# ProDoc_HEMY_Brake_Driver_1_1_2025-03-20.net
KiCad netlist of a schematic drawn in EasyEDA Pro
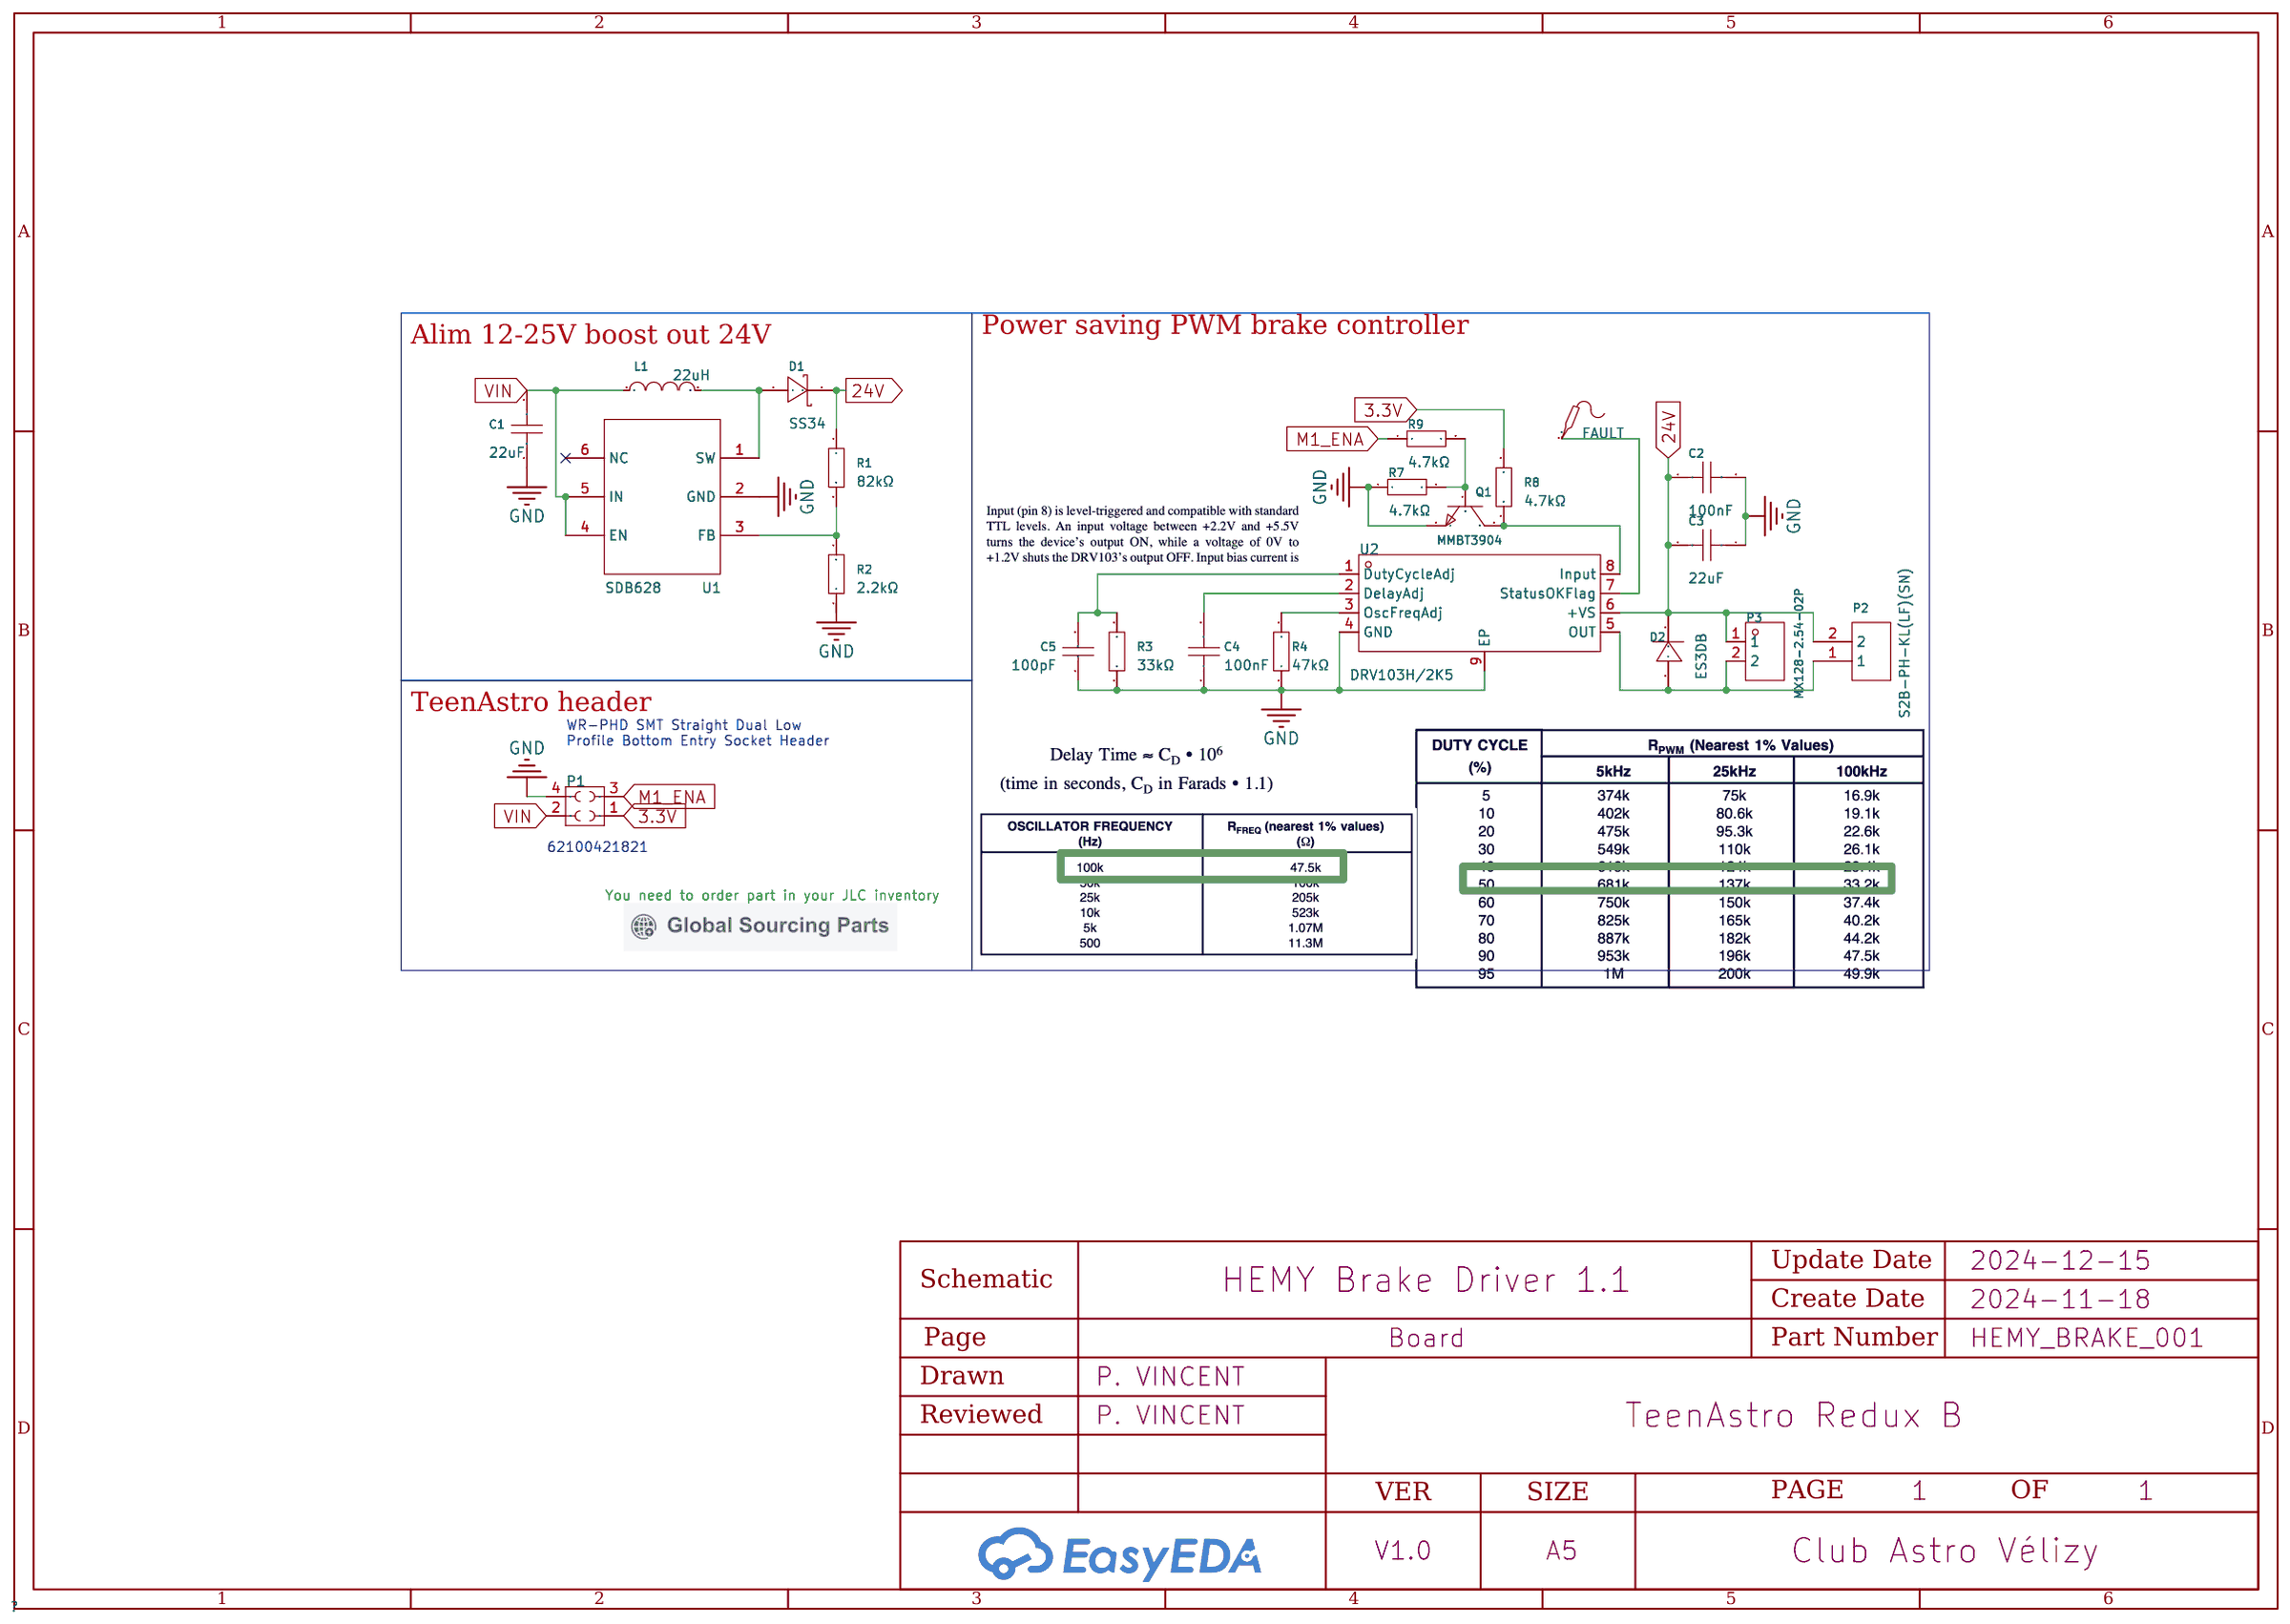
[diagram p0: schematic sheet]

(export (version "E")
  (design (tool "Eeschema 10.0.6"))
  (components
    (comp (ref "C1")
      (value "22uF")
      (footprint "easyedapro:C0805")
      (fields
        (field (name "Manufacturer Part") "CGA0805X5R226M350MT")
        (field (name "Manufacturer") "HRE(芯声)")
      )
      (libsource (lib "easyedapro") (part "CGA0805X5R226M350MT"))
    )
    (comp (ref "C2")
      (value "100nF")
      (footprint "easyedapro:C0805")
      (fields
        (field (name "Manufacturer Part") "CC0805KRX7R9BB104")
        (field (name "Manufacturer") "YAGEO(国巨)")
      )
      (libsource (lib "easyedapro") (part "CC0805KRX7R9BB104"))
    )
    (comp (ref "C3")
      (value "22uF")
      (footprint "easyedapro:C0805")
      (fields
        (field (name "Manufacturer Part") "CGA0805X5R226M350MT")
        (field (name "Manufacturer") "HRE(芯声)")
      )
      (libsource (lib "easyedapro") (part "CGA0805X5R226M350MT"))
    )
    (comp (ref "C4")
      (value "100nF")
      (fields
        (field (name "Manufacturer Part") "CC0603KRX7R9BB104")
        (field (name "Manufacturer") "YAGEO(国巨)")
      )
      (libsource (lib "easyedapro") (part "CC0603KRX7R9BB104"))
    )
    (comp (ref "C5")
      (value "100pF")
      (fields
        (field (name "Manufacturer Part") "CL10C101JB8NNNC")
        (field (name "Manufacturer") "SAMSUNG(三星)")
      )
      (libsource (lib "easyedapro") (part "CL10C101JB8NNNC"))
    )
    (comp (ref "D1")
      (value "SS34")
      (footprint "easyedapro:SMA_L4.3-W2.6-LS5.2-RD")
      (fields (field (name "Manufacturer") "MDD(辰达半导体)"))
      (libsource (lib "easyedapro") (part "SS34_C8678"))
    )
    (comp (ref "D2")
      (value "ES3DB")
      (footprint "easyedapro:SMB_L4.6-W3.6-LS5.3-RD")
      (fields (field (name "Manufacturer") "MDD(辰达半导体)"))
      (libsource (lib "easyedapro") (part "ES3D"))
    )
    (comp (ref "FAULT")
      (value "~")
      (footprint "easyedapro:Test-Point-0.5mm")
      (description "Test Point 测试点")
      (libsource (lib "easyedapro") (part "Test-Point"))
    )
    (comp (ref "L1")
      (value "22uH")
      (footprint "easyedapro:IND-SMD_L7.1-W6.6")
      (fields
        (field (name "Manufacturer Part") "YSPI0630A-220M")
        (field (name "Manufacturer") "YJYCOIN(益嘉源)")
      )
      (libsource (lib "easyedapro") (part "YSPI0630A-220M"))
    )
    (comp (ref "P1")
      (value "~")
      (footprint "easyedapro:62100421821")
      (libsource (lib "easyedapro") (part "6210XX21821_62100421821_"))
    )
    (comp (ref "P2")
      (value "S2B-PH-KL(LF)(SN)")
      (footprint "easyedapro:CONN-TH-2P-P2.00_S2B-PH-KL-LF-SN")
      (fields (field (name "Manufacturer") "JST"))
      (libsource (lib "easyedapro") (part "S2B-PH-KL(LF)(SN)"))
    )
    (comp (ref "P3")
      (value "MX128-2.54-02P")
      (footprint "easyedapro:CONN-TH_2P-P2.54_MX128-2.54-GN01-02P-CU-Y-A")
      (fields (field (name "Manufacturer") "MAX(迈旭)"))
      (libsource (lib "easyedapro") (part "MX128-2.54-02P-GN01-CU-Y-A"))
    )
    (comp (ref "Q1")
      (value "MMBT3904")
      (footprint "easyedapro:SOT-23-3_L2.9-W1.3-P1.90-LS2.4-BR")
      (fields (field (name "Manufacturer") "CJ(江苏长电/长晶)"))
      (libsource (lib "easyedapro") (part "MMBT3904"))
    )
    (comp (ref "R1")
      (value "82kΩ")
      (footprint "easyedapro:R0603")
      (fields
        (field (name "Manufacturer Part") "0603WAF8202T5E")
        (field (name "Manufacturer") "UNI-ROYAL(厚声)")
      )
      (libsource (lib "easyedapro") (part "0603WAF8202T5E"))
    )
    (comp (ref "R2")
      (value "2.2kΩ")
      (footprint "easyedapro:R0603")
      (fields
        (field (name "Manufacturer Part") "0603WAF2201T5E")
        (field (name "Manufacturer") "UNI-ROYAL(厚声)")
      )
      (libsource (lib "easyedapro") (part "0603WAF2201T5E"))
    )
    (comp (ref "R3")
      (value "33kΩ")
      (footprint "easyedapro:R0603")
      (fields
        (field (name "Manufacturer Part") "0603WAF3302T5E")
        (field (name "Manufacturer") "UNI-ROYAL(厚声)")
      )
      (libsource (lib "easyedapro") (part "0603WAF3302T5E"))
    )
    (comp (ref "R4")
      (value "47kΩ")
      (footprint "easyedapro:R0603")
      (fields
        (field (name "Manufacturer Part") "0603WAF4702T5E")
        (field (name "Manufacturer") "UNI-ROYAL(厚声)")
      )
      (libsource (lib "easyedapro") (part "0603WAF4702T5E"))
    )
    (comp (ref "R7")
      (value "4.7kΩ")
      (footprint "easyedapro:R0603")
      (fields
        (field (name "Manufacturer Part") "0603WAF4701T5E")
        (field (name "Manufacturer") "UNI-ROYAL(厚声)")
      )
      (libsource (lib "easyedapro") (part "0603WAF4701T5E"))
    )
    (comp (ref "R8")
      (value "4.7kΩ")
      (footprint "easyedapro:R0603")
      (fields
        (field (name "Manufacturer Part") "0603WAF4701T5E")
        (field (name "Manufacturer") "UNI-ROYAL(厚声)")
      )
      (libsource (lib "easyedapro") (part "0603WAF4701T5E"))
    )
    (comp (ref "R9")
      (value "4.7kΩ")
      (footprint "easyedapro:R0603")
      (fields
        (field (name "Manufacturer Part") "0603WAF4701T5E")
        (field (name "Manufacturer") "UNI-ROYAL(厚声)")
      )
      (libsource (lib "easyedapro") (part "0603WAF4701T5E"))
    )
    (comp (ref "U1")
      (value "SDB628")
      (footprint "easyedapro:SOT-23-6_L2.9-W1.6-P0.95-LS2.8-BR")
      (fields (field (name "Manufacturer") "SHOUDING(首鼎半导体)"))
      (libsource (lib "easyedapro") (part "SDB628"))
    )
    (comp (ref "U2")
      (value "DRV103H/2K5")
      (footprint "easyedapro:SOIC-8_L4.9-W3.9-P1.27-LS6.0-BL-EP2.3")
      (fields (field (name "Manufacturer") "TI(德州仪器)"))
      (libsource (lib "easyedapro") (part "DRV103H/2K5"))
    )
  )
  (nets
    (net (code "1") (name "3.3V") (class "Default")
      (node (ref "P1") (pin "1") (pinfunction "1_1") (pintype "unspecified"))
      (node (ref "R8") (pin "2") (pinfunction "2_2") (pintype "input"))
    )
    (net (code "2") (name "24V") (class "Default")
      (node (ref "C2") (pin "1") (pinfunction "1_1") (pintype "unspecified"))
      (node (ref "C3") (pin "2") (pinfunction "2_2") (pintype "input"))
      (node (ref "D1") (pin "1") (pinfunction "K_1") (pintype "unspecified"))
      (node (ref "D2") (pin "1") (pinfunction "C_1") (pintype "unspecified"))
      (node (ref "P2") (pin "2") (pinfunction "2_2") (pintype "unspecified"))
      (node (ref "P3") (pin "1") (pinfunction "1_1") (pintype "input"))
      (node (ref "R1") (pin "1") (pinfunction "1_1") (pintype "input"))
      (node (ref "U2") (pin "6") (pinfunction "+VS_6") (pintype "unspecified"))
    )
    (net (code "3") (name "GND") (class "Default")
      (node (ref "C1") (pin "1") (pinfunction "1_1") (pintype "input"))
      (node (ref "C2") (pin "2") (pinfunction "2_2") (pintype "unspecified"))
      (node (ref "C3") (pin "1") (pinfunction "1_1") (pintype "input"))
      (node (ref "C4") (pin "1") (pinfunction "1_1") (pintype "input"))
      (node (ref "C5") (pin "1") (pinfunction "1_1") (pintype "input"))
      (node (ref "P1") (pin "4") (pinfunction "4_4") (pintype "unspecified"))
      (node (ref "Q1") (pin "2") (pinfunction "E_2") (pintype "input"))
      (node (ref "R2") (pin "1") (pinfunction "1_1") (pintype "input"))
      (node (ref "R3") (pin "1") (pinfunction "1_1") (pintype "input"))
      (node (ref "R4") (pin "1") (pinfunction "1_1") (pintype "input"))
      (node (ref "R7") (pin "1") (pinfunction "1_1") (pintype "input"))
      (node (ref "U1") (pin "2") (pinfunction "GND_2") (pintype "input"))
      (node (ref "U2") (pin "4") (pinfunction "GND_4") (pintype "unspecified"))
      (node (ref "U2") (pin "9") (pinfunction "EP_9") (pintype "unspecified"))
    )
    (net (code "4") (name "M1_ENA") (class "Default")
      (node (ref "P1") (pin "3") (pinfunction "3_3") (pintype "unspecified"))
      (node (ref "R9") (pin "1") (pinfunction "1_1") (pintype "input"))
    )
    (net (code "5") (name "Net-(D1-A)") (class "Default")
      (node (ref "D1") (pin "2") (pinfunction "A_2") (pintype "unspecified"))
      (node (ref "L1") (pin "2") (pinfunction "2_2") (pintype "input"))
      (node (ref "U1") (pin "1") (pinfunction "SW_1") (pintype "input"))
    )
    (net (code "6") (name "Net-(D2-A)") (class "Default")
      (node (ref "D2") (pin "2") (pinfunction "A_2") (pintype "unspecified"))
      (node (ref "P2") (pin "1") (pinfunction "1_1") (pintype "unspecified"))
      (node (ref "P3") (pin "2") (pinfunction "2_2") (pintype "input"))
      (node (ref "U2") (pin "5") (pinfunction "OUT_5") (pintype "unspecified"))
    )
    (net (code "7") (name "Net-(Q1-B)") (class "Default")
      (node (ref "Q1") (pin "1") (pinfunction "B_1") (pintype "input"))
      (node (ref "R7") (pin "2") (pinfunction "2_2") (pintype "input"))
      (node (ref "R9") (pin "2") (pinfunction "2_2") (pintype "input"))
    )
    (net (code "8") (name "Net-(Q1-C)") (class "Default")
      (node (ref "Q1") (pin "3") (pinfunction "C_3") (pintype "input"))
      (node (ref "R8") (pin "1") (pinfunction "1_1") (pintype "input"))
      (node (ref "U2") (pin "8") (pinfunction "Input_8") (pintype "unspecified"))
    )
    (net (code "9") (name "Net-(U1-FB)") (class "Default")
      (node (ref "R1") (pin "2") (pinfunction "2_2") (pintype "input"))
      (node (ref "R2") (pin "2") (pinfunction "2_2") (pintype "input"))
      (node (ref "U1") (pin "3") (pinfunction "FB_3") (pintype "input"))
    )
    (net (code "10") (name "Net-(U2-DelayAdj)") (class "Default")
      (node (ref "C4") (pin "2") (pinfunction "2_2") (pintype "input"))
      (node (ref "U2") (pin "2") (pinfunction "DelayAdj_2") (pintype "unspecified"))
    )
    (net (code "11") (name "Net-(U2-DutyCycleAdj)") (class "Default")
      (node (ref "C5") (pin "2") (pinfunction "2_2") (pintype "input"))
      (node (ref "R3") (pin "2") (pinfunction "2_2") (pintype "input"))
      (node (ref "U2") (pin "1") (pinfunction "DutyCycleAdj_1") (pintype "unspecified"))
    )
    (net (code "12") (name "Net-(U2-OscFreqAdj)") (class "Default")
      (node (ref "R4") (pin "2") (pinfunction "2_2") (pintype "input"))
      (node (ref "U2") (pin "3") (pinfunction "OscFreqAdj_3") (pintype "unspecified"))
    )
    (net (code "13") (name "Net-(U2-StatusOKFlag)") (class "Default")
      (node (ref "FAULT") (pin "1") (pinfunction "1_1") (pintype "unspecified"))
      (node (ref "U2") (pin "7") (pinfunction "StatusOKFlag_7") (pintype "unspecified"))
    )
    (net (code "14") (name "VIN") (class "Default")
      (node (ref "C1") (pin "2") (pinfunction "2_2") (pintype "input"))
      (node (ref "L1") (pin "1") (pinfunction "1_1") (pintype "input"))
      (node (ref "P1") (pin "2") (pinfunction "2_2") (pintype "unspecified"))
      (node (ref "U1") (pin "4") (pinfunction "EN_4") (pintype "input"))
      (node (ref "U1") (pin "5") (pinfunction "IN_5") (pintype "input"))
    )
    (net (code "15") (name "unconnected-(U1-NC-Pad6)") (class "Default")
      (node (ref "U1") (pin "6") (pinfunction "NC_6") (pintype "input+no_connect"))
    )
  )
)
